# shield_v8.net
KiCad netlist of a schematic drawn in EAGLE
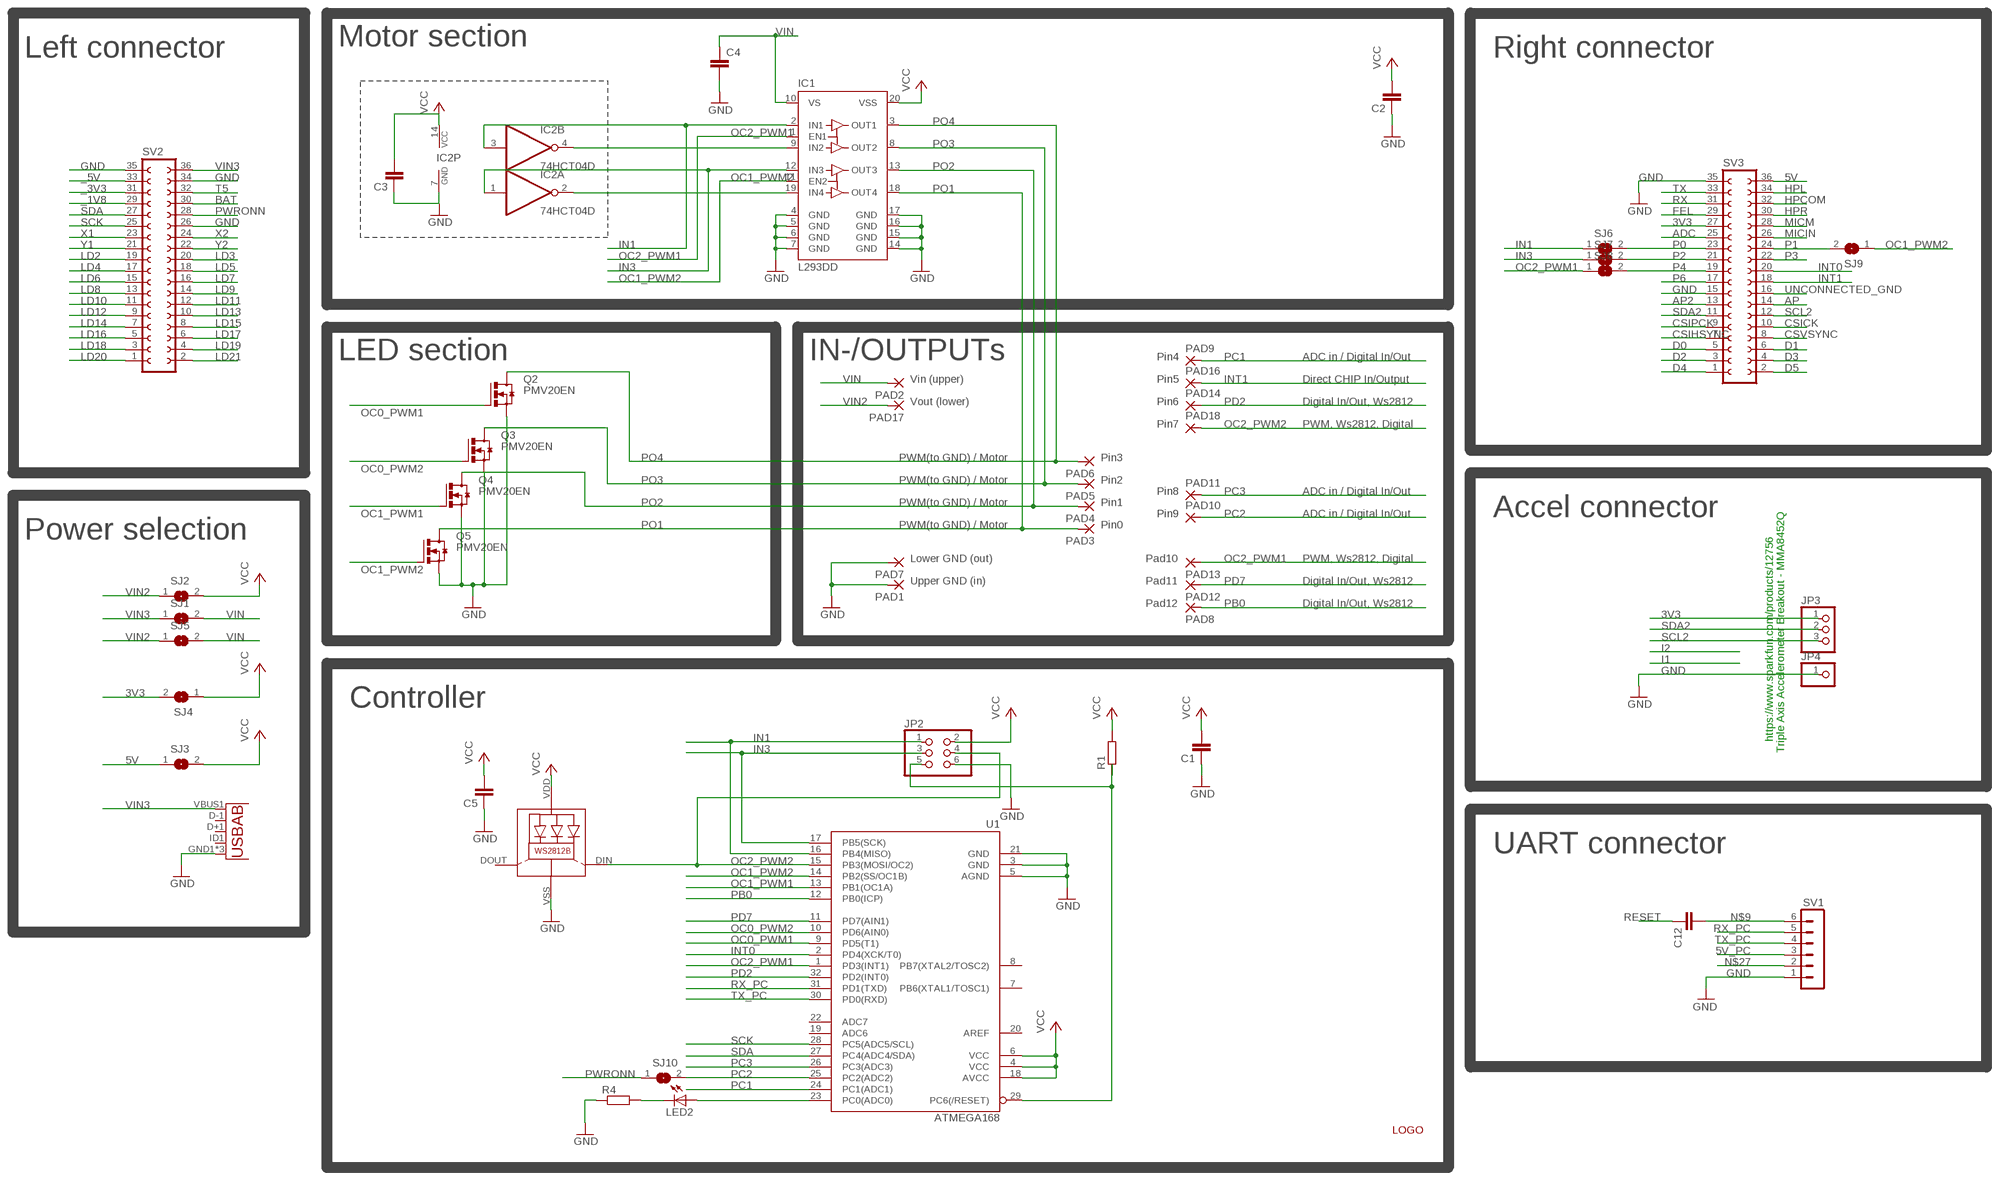
[diagram p0: schematic, sheet 1]

(export (version "E")
  (design (tool "Eeschema 10.0.6"))
  (components
    (comp (ref "C1")
      (value "C-EUC0805")
      (footprint "eagle-import:C0805")
      (libsource (lib "eagle-import") (part "C-EUC0805"))
    )
    (comp (ref "C2")
      (value "C-EUC0805")
      (footprint "eagle-import:C0805")
      (libsource (lib "eagle-import") (part "C-EUC0805"))
    )
    (comp (ref "C3")
      (value "C-EUC0805")
      (footprint "eagle-import:C0805")
      (libsource (lib "eagle-import") (part "C-EUC0805"))
    )
    (comp (ref "C4")
      (value "C-EUC1210")
      (footprint "eagle-import:C1210")
      (libsource (lib "eagle-import") (part "C-EUC1210"))
    )
    (comp (ref "C5")
      (value "C-EUC0805")
      (footprint "eagle-import:C0805")
      (libsource (lib "eagle-import") (part "C-EUC0805"))
    )
    (comp (ref "C12")
      (value "C-EUC1206")
      (footprint "eagle-import:C1206")
      (libsource (lib "eagle-import") (part "C-EUC1206"))
    )
    (comp (ref "IC1")
      (value "L293DD")
      (footprint "eagle-import:SO20")
      (libsource (lib "eagle-import") (part "L293DD"))
    )
    (comp (ref "IC2")
      (value "74HCT04D")
      (footprint "eagle-import:SO14")
      (libsource (lib "eagle-import") (part "7404DHCT"))
    )
    (comp (ref "JP2")
      (value "PINHD-2X3")
      (footprint "eagle-import:2X03")
      (libsource (lib "eagle-import") (part "PINHD-2X3"))
    )
    (comp (ref "JP3")
      (value "PINHD-1X3")
      (footprint "eagle-import:1X03")
      (libsource (lib "eagle-import") (part "PINHD-1X3"))
    )
    (comp (ref "JP4")
      (value "PINHD-1X1")
      (footprint "eagle-import:1X01")
      (libsource (lib "eagle-import") (part "PINHD-1X1"))
    )
    (comp (ref "LED1")
      (value "WS2812B")
      (footprint "eagle-import:WS2812B")
      (libsource (lib "eagle-import") (part "WS2812B"))
    )
    (comp (ref "LED2")
      (value "LEDCHIP-LED0805")
      (footprint "eagle-import:CHIP-LED0805")
      (libsource (lib "eagle-import") (part "LEDCHIP-LED0805"))
    )
    (comp (ref "PAD1")
      (value "3,17/1,3")
      (footprint "eagle-import:3,17_1,3")
      (libsource (lib "eagle-import") (part "3,17/1,3"))
    )
    (comp (ref "PAD2")
      (value "3,17/1,3")
      (footprint "eagle-import:3,17_1,3")
      (libsource (lib "eagle-import") (part "3,17/1,3"))
    )
    (comp (ref "PAD3")
      (value "3,17/1,3")
      (footprint "eagle-import:3,17_1,3")
      (libsource (lib "eagle-import") (part "3,17/1,3"))
    )
    (comp (ref "PAD4")
      (value "3,17/1,3")
      (footprint "eagle-import:3,17_1,3")
      (libsource (lib "eagle-import") (part "3,17/1,3"))
    )
    (comp (ref "PAD5")
      (value "3,17/1,3")
      (footprint "eagle-import:3,17_1,3")
      (libsource (lib "eagle-import") (part "3,17/1,3"))
    )
    (comp (ref "PAD6")
      (value "3,17/1,3")
      (footprint "eagle-import:3,17_1,3")
      (libsource (lib "eagle-import") (part "3,17/1,3"))
    )
    (comp (ref "PAD7")
      (value "3,17/1,3")
      (footprint "eagle-import:3,17_1,3")
      (libsource (lib "eagle-import") (part "3,17/1,3"))
    )
    (comp (ref "PAD8")
      (value "WIREPADSMD1,27-254")
      (footprint "eagle-import:SMD1,27-2,54")
      (libsource (lib "eagle-import") (part "WIREPADSMD1,27-254"))
    )
    (comp (ref "PAD9")
      (value "3,17/1,3")
      (footprint "eagle-import:3,17_1,3")
      (libsource (lib "eagle-import") (part "3,17/1,3"))
    )
    (comp (ref "PAD10")
      (value "3,17/1,3")
      (footprint "eagle-import:3,17_1,3")
      (libsource (lib "eagle-import") (part "3,17/1,3"))
    )
    (comp (ref "PAD11")
      (value "3,17/1,3")
      (footprint "eagle-import:3,17_1,3")
      (libsource (lib "eagle-import") (part "3,17/1,3"))
    )
    (comp (ref "PAD12")
      (value "SMD2")
      (footprint "eagle-import:SMD1,27-2,54")
      (libsource (lib "eagle-import") (part "SMD2"))
    )
    (comp (ref "PAD13")
      (value "SMD2")
      (footprint "eagle-import:SMD1,27-2,54")
      (libsource (lib "eagle-import") (part "SMD2"))
    )
    (comp (ref "PAD14")
      (value "3,17/1,3")
      (footprint "eagle-import:3,17_1,3")
      (libsource (lib "eagle-import") (part "3,17/1,3"))
    )
    (comp (ref "PAD16")
      (value "3,17/1,3")
      (footprint "eagle-import:3,17_1,3")
      (libsource (lib "eagle-import") (part "3,17/1,3"))
    )
    (comp (ref "PAD17")
      (value "3,17/1,3")
      (footprint "eagle-import:3,17_1,3")
      (libsource (lib "eagle-import") (part "3,17/1,3"))
    )
    (comp (ref "PAD18")
      (value "3,17/1,3")
      (footprint "eagle-import:3,17_1,3")
      (libsource (lib "eagle-import") (part "3,17/1,3"))
    )
    (comp (ref "Q2")
      (value "PMV20EN")
      (footprint "eagle-import:SOT223")
      (libsource (lib "eagle-import") (part "NMOSFET_SMD_223"))
    )
    (comp (ref "Q3")
      (value "PMV20EN")
      (footprint "eagle-import:SOT223")
      (libsource (lib "eagle-import") (part "NMOSFET_SMD_223"))
    )
    (comp (ref "Q4")
      (value "PMV20EN")
      (footprint "eagle-import:SOT223")
      (libsource (lib "eagle-import") (part "NMOSFET_SMD_223"))
    )
    (comp (ref "Q5")
      (value "PMV20EN")
      (footprint "eagle-import:SOT223")
      (libsource (lib "eagle-import") (part "NMOSFET_SMD_223"))
    )
    (comp (ref "R1")
      (value "R-EU_M1206")
      (footprint "eagle-import:M1206")
      (libsource (lib "eagle-import") (part "R-EU_M1206"))
    )
    (comp (ref "R4")
      (value "R-EU_M1206")
      (footprint "eagle-import:M1206")
      (libsource (lib "eagle-import") (part "R-EU_M1206"))
    )
    (comp (ref "SJ1") (value "SJ") (footprint "eagle-import:SJ") (libsource (lib "eagle-import") (part "SJ")))
    (comp (ref "SJ2") (value "SJ") (footprint "eagle-import:SJ") (libsource (lib "eagle-import") (part "SJ")))
    (comp (ref "SJ3") (value "SJ") (footprint "eagle-import:SJ") (libsource (lib "eagle-import") (part "SJ")))
    (comp (ref "SJ4") (value "SJ") (footprint "eagle-import:SJ") (libsource (lib "eagle-import") (part "SJ")))
    (comp (ref "SJ5") (value "SJ") (footprint "eagle-import:SJ") (libsource (lib "eagle-import") (part "SJ")))
    (comp (ref "SJ6") (value "SJ") (footprint "eagle-import:SJ") (libsource (lib "eagle-import") (part "SJ")))
    (comp (ref "SJ7") (value "SJ") (footprint "eagle-import:SJ") (libsource (lib "eagle-import") (part "SJ")))
    (comp (ref "SJ8") (value "SJ") (footprint "eagle-import:SJ") (libsource (lib "eagle-import") (part "SJ")))
    (comp (ref "SJ9") (value "SJ") (footprint "eagle-import:SJ") (libsource (lib "eagle-import") (part "SJ")))
    (comp (ref "SJ10")
      (value "SJ")
      (footprint "eagle-import:SJ")
      (libsource (lib "eagle-import") (part "SJ"))
    )
    (comp (ref "SV1")
      (value "MA06-1")
      (footprint "eagle-import:MA06-1")
      (libsource (lib "eagle-import") (part "MA06-1"))
    )
    (comp (ref "SV2")
      (value "FE18-2")
      (footprint "eagle-import:FE18-2")
      (libsource (lib "eagle-import") (part "FE18-2"))
    )
    (comp (ref "SV3")
      (value "FE18-2")
      (footprint "eagle-import:FE18-2")
      (libsource (lib "eagle-import") (part "FE18-2"))
    )
    (comp (ref "U$2")
      (value "LOGO")
      (footprint "eagle-import:LOGO")
      (libsource (lib "eagle-import") (part "LOGO"))
    )
    (comp (ref "U1")
      (value "ATMEGA168")
      (footprint "eagle-import:TQFP32-08")
      (libsource (lib "eagle-import") (part "ATMEGA168"))
    )
    (comp (ref "U2")
      (value "USB\"\"")
      (footprint "eagle-import:USB-MICRO-SMD")
      (libsource (lib "eagle-import") (part "USB{dblquote}{dblquote}"))
    )
  )
  (nets
    (net (code "1") (name "/3V3") (class "Default")
      (node (ref "JP3") (pin "1") (pinfunction "1_1") (pintype "passive"))
      (node (ref "SJ4") (pin "2") (pinfunction "2_2") (pintype "passive"))
      (node (ref "SV3") (pin "27") (pinfunction "27_27") (pintype "passive"))
    )
    (net (code "2") (name "/5V") (class "Default")
      (node (ref "SJ3") (pin "1") (pinfunction "1_1") (pintype "passive"))
      (node (ref "SV3") (pin "36") (pinfunction "36_36") (pintype "passive"))
    )
    (net (code "3") (name "/5V_PC") (class "Default")
      (node (ref "SV1") (pin "3") (pinfunction "3_3") (pintype "passive"))
    )
    (net (code "4") (name "/ADC") (class "Default")
      (node (ref "SV3") (pin "25") (pinfunction "25_25") (pintype "passive"))
    )
    (net (code "5") (name "/AP") (class "Default")
      (node (ref "SV3") (pin "14") (pinfunction "14_14") (pintype "passive"))
    )
    (net (code "6") (name "/AP2") (class "Default")
      (node (ref "SV3") (pin "13") (pinfunction "13_13") (pintype "passive"))
    )
    (net (code "7") (name "/BAT") (class "Default")
      (node (ref "SV2") (pin "30") (pinfunction "30_30") (pintype "passive"))
    )
    (net (code "8") (name "/CSICK") (class "Default")
      (node (ref "SV3") (pin "10") (pinfunction "10_10") (pintype "passive"))
    )
    (net (code "9") (name "/CSIHSYNC") (class "Default")
      (node (ref "SV3") (pin "7") (pinfunction "7_7") (pintype "passive"))
    )
    (net (code "10") (name "/CSIPCK") (class "Default")
      (node (ref "SV3") (pin "9") (pinfunction "9_9") (pintype "passive"))
    )
    (net (code "11") (name "/CSVSYNC") (class "Default")
      (node (ref "SV3") (pin "8") (pinfunction "8_8") (pintype "passive"))
    )
    (net (code "12") (name "/D0") (class "Default")
      (node (ref "SV3") (pin "5") (pinfunction "5_5") (pintype "passive"))
    )
    (net (code "13") (name "/D1") (class "Default")
      (node (ref "SV3") (pin "6") (pinfunction "6_6") (pintype "passive"))
    )
    (net (code "14") (name "/D2") (class "Default")
      (node (ref "SV3") (pin "3") (pinfunction "3_3") (pintype "passive"))
    )
    (net (code "15") (name "/D3") (class "Default")
      (node (ref "SV3") (pin "4") (pinfunction "4_4") (pintype "passive"))
    )
    (net (code "16") (name "/D4") (class "Default")
      (node (ref "SV3") (pin "1") (pinfunction "1_1") (pintype "passive"))
    )
    (net (code "17") (name "/D5") (class "Default")
      (node (ref "SV3") (pin "2") (pinfunction "2_2") (pintype "passive"))
    )
    (net (code "18") (name "/FEL") (class "Default")
      (node (ref "SV3") (pin "29") (pinfunction "29_29") (pintype "passive"))
    )
    (net (code "19") (name "/HPCOM") (class "Default")
      (node (ref "SV3") (pin "32") (pinfunction "32_32") (pintype "passive"))
    )
    (net (code "20") (name "/HPL") (class "Default")
      (node (ref "SV3") (pin "34") (pinfunction "34_34") (pintype "passive"))
    )
    (net (code "21") (name "/HPR") (class "Default")
      (node (ref "SV3") (pin "30") (pinfunction "30_30") (pintype "passive"))
    )
    (net (code "24") (name "/IN1") (class "Default")
      (node (ref "IC1") (pin "2") (pinfunction "IN1_2") (pintype "input"))
      (node (ref "IC2") (pin "3") (pinfunction "I_3") (pintype "input"))
      (node (ref "JP2") (pin "1") (pinfunction "1_1") (pintype "passive"))
      (node (ref "SJ6") (pin "1") (pinfunction "1_1") (pintype "passive"))
      (node (ref "U1") (pin "16") (pinfunction "PB4(MISO)_16") (pintype "bidirectional"))
    )
    (net (code "25") (name "/IN3") (class "Default")
      (node (ref "IC1") (pin "12") (pinfunction "IN3_12") (pintype "input"))
      (node (ref "IC2") (pin "1") (pinfunction "I_1") (pintype "input"))
      (node (ref "JP2") (pin "3") (pinfunction "3_3") (pintype "passive"))
      (node (ref "SJ7") (pin "1") (pinfunction "1_1") (pintype "passive"))
      (node (ref "U1") (pin "17") (pinfunction "PB5(SCK)_17") (pintype "bidirectional"))
    )
    (net (code "26") (name "/INT0") (class "Default")
      (node (ref "SV3") (pin "20") (pinfunction "20_20") (pintype "passive"))
      (node (ref "U1") (pin "2") (pinfunction "PD4(XCK/T0)_2") (pintype "bidirectional"))
    )
    (net (code "27") (name "/INT1") (class "Default")
      (node (ref "PAD16") (pin "1") (pinfunction "P_1") (pintype "passive"))
      (node (ref "SV3") (pin "18") (pinfunction "18_18") (pintype "passive"))
    )
    (net (code "28") (name "/LD2") (class "Default")
      (node (ref "SV2") (pin "19") (pinfunction "19_19") (pintype "passive"))
    )
    (net (code "29") (name "/LD3") (class "Default")
      (node (ref "SV2") (pin "20") (pinfunction "20_20") (pintype "passive"))
    )
    (net (code "30") (name "/LD4") (class "Default")
      (node (ref "SV2") (pin "17") (pinfunction "17_17") (pintype "passive"))
    )
    (net (code "31") (name "/LD5") (class "Default")
      (node (ref "SV2") (pin "18") (pinfunction "18_18") (pintype "passive"))
    )
    (net (code "32") (name "/LD6") (class "Default")
      (node (ref "SV2") (pin "15") (pinfunction "15_15") (pintype "passive"))
    )
    (net (code "33") (name "/LD7") (class "Default")
      (node (ref "SV2") (pin "16") (pinfunction "16_16") (pintype "passive"))
    )
    (net (code "34") (name "/LD8") (class "Default")
      (node (ref "SV2") (pin "13") (pinfunction "13_13") (pintype "passive"))
    )
    (net (code "35") (name "/LD9") (class "Default")
      (node (ref "SV2") (pin "14") (pinfunction "14_14") (pintype "passive"))
    )
    (net (code "36") (name "/LD10") (class "Default")
      (node (ref "SV2") (pin "11") (pinfunction "11_11") (pintype "passive"))
    )
    (net (code "37") (name "/LD11") (class "Default")
      (node (ref "SV2") (pin "12") (pinfunction "12_12") (pintype "passive"))
    )
    (net (code "38") (name "/LD12") (class "Default")
      (node (ref "SV2") (pin "9") (pinfunction "9_9") (pintype "passive"))
    )
    (net (code "39") (name "/LD13") (class "Default")
      (node (ref "SV2") (pin "10") (pinfunction "10_10") (pintype "passive"))
    )
    (net (code "40") (name "/LD14") (class "Default")
      (node (ref "SV2") (pin "7") (pinfunction "7_7") (pintype "passive"))
    )
    (net (code "41") (name "/LD15") (class "Default")
      (node (ref "SV2") (pin "8") (pinfunction "8_8") (pintype "passive"))
    )
    (net (code "42") (name "/LD16") (class "Default")
      (node (ref "SV2") (pin "5") (pinfunction "5_5") (pintype "passive"))
    )
    (net (code "43") (name "/LD17") (class "Default")
      (node (ref "SV2") (pin "6") (pinfunction "6_6") (pintype "passive"))
    )
    (net (code "44") (name "/LD18") (class "Default")
      (node (ref "SV2") (pin "3") (pinfunction "3_3") (pintype "passive"))
    )
    (net (code "45") (name "/LD19") (class "Default")
      (node (ref "SV2") (pin "4") (pinfunction "4_4") (pintype "passive"))
    )
    (net (code "46") (name "/LD20") (class "Default")
      (node (ref "SV2") (pin "1") (pinfunction "1_1") (pintype "passive"))
    )
    (net (code "47") (name "/LD21") (class "Default")
      (node (ref "SV2") (pin "2") (pinfunction "2_2") (pintype "passive"))
    )
    (net (code "48") (name "/MICIN") (class "Default")
      (node (ref "SV3") (pin "26") (pinfunction "26_26") (pintype "passive"))
    )
    (net (code "49") (name "/MICM") (class "Default")
      (node (ref "SV3") (pin "28") (pinfunction "28_28") (pintype "passive"))
    )
    (net (code "50") (name "/N$9") (class "Default")
      (node (ref "C12") (pin "2") (pinfunction "2_2") (pintype "passive"))
      (node (ref "SV1") (pin "6") (pinfunction "6_6") (pintype "passive"))
    )
    (net (code "51") (name "/N$27") (class "Default")
      (node (ref "SV1") (pin "2") (pinfunction "2_2") (pintype "passive"))
    )
    (net (code "52") (name "/OC0_PWM1") (class "Default")
      (node (ref "Q2") (pin "1") (pinfunction "G_1") (pintype "passive"))
      (node (ref "U1") (pin "9") (pinfunction "PD5(T1)_9") (pintype "bidirectional"))
    )
    (net (code "53") (name "/OC0_PWM2") (class "Default")
      (node (ref "Q3") (pin "1") (pinfunction "G_1") (pintype "passive"))
      (node (ref "U1") (pin "10") (pinfunction "PD6(AIN0)_10") (pintype "bidirectional"))
    )
    (net (code "54") (name "/OC1_PWM1") (class "Default")
      (node (ref "Q4") (pin "1") (pinfunction "G_1") (pintype "passive"))
      (node (ref "U1") (pin "13") (pinfunction "PB1(OC1A)_13") (pintype "bidirectional"))
    )
    (net (code "55") (name "/OC1_PWM2") (class "Default")
      (node (ref "IC1") (pin "11") (pinfunction "EN2_11") (pintype "input"))
      (node (ref "Q5") (pin "1") (pinfunction "G_1") (pintype "passive"))
      (node (ref "SJ9") (pin "1") (pinfunction "1_1") (pintype "passive"))
      (node (ref "U1") (pin "14") (pinfunction "PB2(SS/OC1B)_14") (pintype "bidirectional"))
    )
    (net (code "56") (name "/OC2_PWM1") (class "Default")
      (node (ref "IC1") (pin "1") (pinfunction "EN1_1") (pintype "input"))
      (node (ref "PAD13") (pin "1") (pinfunction "P_1") (pintype "passive"))
      (node (ref "SJ8") (pin "1") (pinfunction "1_1") (pintype "passive"))
      (node (ref "U1") (pin "1") (pinfunction "PD3(INT1)_1") (pintype "bidirectional"))
    )
    (net (code "57") (name "/OC2_PWM2") (class "Default")
      (node (ref "JP2") (pin "4") (pinfunction "4_4") (pintype "passive"))
      (node (ref "LED1") (pin "DIN") (pinfunction "DI_DIN") (pintype "input"))
      (node (ref "PAD18") (pin "1") (pinfunction "P_1") (pintype "passive"))
      (node (ref "U1") (pin "15") (pinfunction "PB3(MOSI/OC2)_15") (pintype "bidirectional"))
    )
    (net (code "58") (name "/P0") (class "Default")
      (node (ref "SJ6") (pin "2") (pinfunction "2_2") (pintype "passive"))
      (node (ref "SV3") (pin "23") (pinfunction "23_23") (pintype "passive"))
    )
    (net (code "59") (name "/P1") (class "Default")
      (node (ref "SJ9") (pin "2") (pinfunction "2_2") (pintype "passive"))
      (node (ref "SV3") (pin "24") (pinfunction "24_24") (pintype "passive"))
    )
    (net (code "60") (name "/P2") (class "Default")
      (node (ref "SJ7") (pin "2") (pinfunction "2_2") (pintype "passive"))
      (node (ref "SV3") (pin "21") (pinfunction "21_21") (pintype "passive"))
    )
    (net (code "61") (name "/P3") (class "Default")
      (node (ref "SV3") (pin "22") (pinfunction "22_22") (pintype "passive"))
    )
    (net (code "62") (name "/P4") (class "Default")
      (node (ref "SJ8") (pin "2") (pinfunction "2_2") (pintype "passive"))
      (node (ref "SV3") (pin "19") (pinfunction "19_19") (pintype "passive"))
    )
    (net (code "63") (name "/P6") (class "Default")
      (node (ref "SV3") (pin "17") (pinfunction "17_17") (pintype "passive"))
    )
    (net (code "64") (name "/PB0") (class "Default")
      (node (ref "PAD8") (pin "1") (pinfunction "P_1") (pintype "passive"))
      (node (ref "U1") (pin "12") (pinfunction "PB0(ICP)_12") (pintype "bidirectional"))
    )
    (net (code "65") (name "/PC1") (class "Default")
      (node (ref "PAD9") (pin "1") (pinfunction "P_1") (pintype "passive"))
      (node (ref "U1") (pin "24") (pinfunction "PC1(ADC1)_24") (pintype "bidirectional"))
    )
    (net (code "66") (name "/PC2") (class "Default")
      (node (ref "PAD10") (pin "1") (pinfunction "P_1") (pintype "passive"))
      (node (ref "SJ10") (pin "2") (pinfunction "2_2") (pintype "passive"))
      (node (ref "U1") (pin "25") (pinfunction "PC2(ADC2)_25") (pintype "bidirectional"))
    )
    (net (code "67") (name "/PC3") (class "Default")
      (node (ref "PAD11") (pin "1") (pinfunction "P_1") (pintype "passive"))
      (node (ref "U1") (pin "26") (pinfunction "PC3(ADC3)_26") (pintype "bidirectional"))
    )
    (net (code "68") (name "/PD2") (class "Default")
      (node (ref "PAD14") (pin "1") (pinfunction "P_1") (pintype "passive"))
      (node (ref "U1") (pin "32") (pinfunction "PD2(INT0)_32") (pintype "bidirectional"))
    )
    (net (code "69") (name "/PD7") (class "Default")
      (node (ref "PAD12") (pin "1") (pinfunction "P_1") (pintype "passive"))
      (node (ref "U1") (pin "11") (pinfunction "PD7(AIN1)_11") (pintype "bidirectional"))
    )
    (net (code "70") (name "/PO1") (class "Default")
      (node (ref "IC1") (pin "18") (pinfunction "OUT4_18") (pintype "output"))
      (node (ref "PAD3") (pin "1") (pinfunction "P_1") (pintype "passive"))
      (node (ref "Q5") (pin "2") (pinfunction "D_2") (pintype "passive"))
      (node (ref "Q5") (pin "4") (pinfunction "D_4") (pintype "passive"))
    )
    (net (code "71") (name "/PO2") (class "Default")
      (node (ref "IC1") (pin "13") (pinfunction "OUT3_13") (pintype "output"))
      (node (ref "PAD4") (pin "1") (pinfunction "P_1") (pintype "passive"))
      (node (ref "Q4") (pin "2") (pinfunction "D_2") (pintype "passive"))
      (node (ref "Q4") (pin "4") (pinfunction "D_4") (pintype "passive"))
    )
    (net (code "72") (name "/PO3") (class "Default")
      (node (ref "IC1") (pin "8") (pinfunction "OUT2_8") (pintype "output"))
      (node (ref "PAD5") (pin "1") (pinfunction "P_1") (pintype "passive"))
      (node (ref "Q3") (pin "2") (pinfunction "D_2") (pintype "passive"))
      (node (ref "Q3") (pin "4") (pinfunction "D_4") (pintype "passive"))
    )
    (net (code "73") (name "/PO4") (class "Default")
      (node (ref "IC1") (pin "3") (pinfunction "OUT1_3") (pintype "output"))
      (node (ref "PAD6") (pin "1") (pinfunction "P_1") (pintype "passive"))
      (node (ref "Q2") (pin "2") (pinfunction "D_2") (pintype "passive"))
      (node (ref "Q2") (pin "4") (pinfunction "D_4") (pintype "passive"))
    )
    (net (code "74") (name "/PWRONN") (class "Default")
      (node (ref "SJ10") (pin "1") (pinfunction "1_1") (pintype "passive"))
      (node (ref "SV2") (pin "28") (pinfunction "28_28") (pintype "passive"))
    )
    (net (code "75") (name "/RESET") (class "Default")
      (node (ref "C12") (pin "1") (pinfunction "1_1") (pintype "passive"))
      (node (ref "JP2") (pin "5") (pinfunction "5_5") (pintype "passive"))
      (node (ref "R1") (pin "1") (pinfunction "1_1") (pintype "passive"))
      (node (ref "U1") (pin "29") (pinfunction "PC6(/RESET)_29") (pintype "bidirectional"))
    )
    (net (code "76") (name "/RX") (class "Default")
      (node (ref "SV3") (pin "31") (pinfunction "31_31") (pintype "passive"))
    )
    (net (code "77") (name "/RX_PC") (class "Default")
      (node (ref "SV1") (pin "5") (pinfunction "5_5") (pintype "passive"))
      (node (ref "U1") (pin "31") (pinfunction "PD1(TXD)_31") (pintype "bidirectional"))
    )
    (net (code "78") (name "/SCK") (class "Default")
      (node (ref "SV2") (pin "25") (pinfunction "25_25") (pintype "passive"))
      (node (ref "U1") (pin "28") (pinfunction "PC5(ADC5/SCL)_28") (pintype "bidirectional"))
    )
    (net (code "79") (name "/SCL2") (class "Default")
      (node (ref "JP3") (pin "3") (pinfunction "3_3") (pintype "passive"))
      (node (ref "SV3") (pin "12") (pinfunction "12_12") (pintype "passive"))
    )
    (net (code "80") (name "/SDA") (class "Default")
      (node (ref "SV2") (pin "27") (pinfunction "27_27") (pintype "passive"))
      (node (ref "U1") (pin "27") (pinfunction "PC4(ADC4/SDA)_27") (pintype "bidirectional"))
    )
    (net (code "81") (name "/SDA2") (class "Default")
      (node (ref "JP3") (pin "2") (pinfunction "2_2") (pintype "passive"))
      (node (ref "SV3") (pin "11") (pinfunction "11_11") (pintype "passive"))
    )
    (net (code "82") (name "/T5") (class "Default")
      (node (ref "SV2") (pin "32") (pinfunction "32_32") (pintype "passive"))
    )
    (net (code "83") (name "/TX") (class "Default")
      (node (ref "SV3") (pin "33") (pinfunction "33_33") (pintype "passive"))
    )
    (net (code "84") (name "/TX_PC") (class "Default")
      (node (ref "SV1") (pin "4") (pinfunction "4_4") (pintype "passive"))
      (node (ref "U1") (pin "30") (pinfunction "PD0(RXD)_30") (pintype "bidirectional"))
    )
    (net (code "85") (name "/UNCONNECTED_GND") (class "Default")
      (node (ref "SV3") (pin "16") (pinfunction "16_16") (pintype "passive"))
    )
    (net (code "86") (name "/VIN") (class "Default")
      (node (ref "C4") (pin "1") (pinfunction "1_1") (pintype "passive"))
      (node (ref "IC1") (pin "10") (pinfunction "VS_10") (pintype "power_in"))
      (node (ref "PAD2") (pin "1") (pinfunction "P_1") (pintype "passive"))
      (node (ref "SJ1") (pin "2") (pinfunction "2_2") (pintype "passive"))
      (node (ref "SJ5") (pin "2") (pinfunction "2_2") (pintype "passive"))
    )
    (net (code "87") (name "/VIN2") (class "Default")
      (node (ref "PAD17") (pin "1") (pinfunction "P_1") (pintype "passive"))
      (node (ref "SJ2") (pin "1") (pinfunction "1_1") (pintype "passive"))
      (node (ref "SJ5") (pin "1") (pinfunction "1_1") (pintype "passive"))
    )
    (net (code "88") (name "/VIN3") (class "Default")
      (node (ref "SJ1") (pin "1") (pinfunction "1_1") (pintype "passive"))
      (node (ref "SV2") (pin "36") (pinfunction "36_36") (pintype "passive"))
      (node (ref "U2") (pin "VBUS1") (pinfunction "VBUS_VBUS1") (pintype "bidirectional"))
    )
    (net (code "89") (name "/X1") (class "Default")
      (node (ref "SV2") (pin "23") (pinfunction "23_23") (pintype "passive"))
    )
    (net (code "90") (name "/X2") (class "Default")
      (node (ref "SV2") (pin "24") (pinfunction "24_24") (pintype "passive"))
    )
    (net (code "91") (name "/Y1") (class "Default")
      (node (ref "SV2") (pin "21") (pinfunction "21_21") (pintype "passive"))
    )
    (net (code "92") (name "/Y2") (class "Default")
      (node (ref "SV2") (pin "22") (pinfunction "22_22") (pintype "passive"))
    )
    (net (code "93") (name "/_1V8") (class "Default")
      (node (ref "SV2") (pin "29") (pinfunction "29_29") (pintype "passive"))
    )
    (net (code "94") (name "/_3V3") (class "Default")
      (node (ref "SV2") (pin "31") (pinfunction "31_31") (pintype "passive"))
    )
    (net (code "95") (name "/_5V") (class "Default")
      (node (ref "SV2") (pin "33") (pinfunction "33_33") (pintype "passive"))
    )
    (net (code "96") (name "GND") (class "Default")
      (node (ref "C1") (pin "1") (pinfunction "1_1") (pintype "passive"))
      (node (ref "C2") (pin "1") (pinfunction "1_1") (pintype "passive"))
      (node (ref "C3") (pin "1") (pinfunction "1_1") (pintype "passive"))
      (node (ref "C4") (pin "2") (pinfunction "2_2") (pintype "passive"))
      (node (ref "C5") (pin "1") (pinfunction "1_1") (pintype "passive"))
      (node (ref "IC1") (pin "14") (pinfunction "GND_14") (pintype "power_in"))
      (node (ref "IC1") (pin "15") (pinfunction "GND_15") (pintype "power_in"))
      (node (ref "IC1") (pin "16") (pinfunction "GND_16") (pintype "power_in"))
      (node (ref "IC1") (pin "17") (pinfunction "GND_17") (pintype "power_in"))
      (node (ref "IC1") (pin "4") (pinfunction "GND_4") (pintype "power_in"))
      (node (ref "IC1") (pin "5") (pinfunction "GND_5") (pintype "power_in"))
      (node (ref "IC1") (pin "6") (pinfunction "GND_6") (pintype "power_in"))
      (node (ref "IC1") (pin "7") (pinfunction "GND_7") (pintype "power_in"))
      (node (ref "IC2") (pin "7") (pinfunction "GND_7") (pintype "power_in"))
      (node (ref "JP2") (pin "6") (pinfunction "6_6") (pintype "passive"))
      (node (ref "JP4") (pin "1") (pinfunction "1_1") (pintype "passive"))
      (node (ref "LED1") (pin "VSS") (pinfunction "GND_VSS") (pintype "power_in"))
      (node (ref "PAD1") (pin "1") (pinfunction "P_1") (pintype "passive"))
      (node (ref "PAD7") (pin "1") (pinfunction "P_1") (pintype "passive"))
      (node (ref "Q2") (pin "3") (pinfunction "S_3") (pintype "passive"))
      (node (ref "Q3") (pin "3") (pinfunction "S_3") (pintype "passive"))
      (node (ref "Q4") (pin "3") (pinfunction "S_3") (pintype "passive"))
      (node (ref "Q5") (pin "3") (pinfunction "S_3") (pintype "passive"))
      (node (ref "R4") (pin "1") (pinfunction "1_1") (pintype "passive"))
      (node (ref "SV1") (pin "1") (pinfunction "1_1") (pintype "passive"))
      (node (ref "SV2") (pin "26") (pinfunction "26_26") (pintype "passive"))
      (node (ref "SV2") (pin "34") (pinfunction "34_34") (pintype "passive"))
      (node (ref "SV2") (pin "35") (pinfunction "35_35") (pintype "passive"))
      (node (ref "SV3") (pin "15") (pinfunction "15_15") (pintype "passive"))
      (node (ref "SV3") (pin "35") (pinfunction "35_35") (pintype "passive"))
      (node (ref "U1") (pin "21") (pinfunction "GND_21") (pintype "bidirectional"))
      (node (ref "U1") (pin "3") (pinfunction "GND_3") (pintype "bidirectional"))
      (node (ref "U1") (pin "5") (pinfunction "AGND_5") (pintype "bidirectional"))
      (node (ref "U2") (pin "GND1") (pinfunction "GND_GND1") (pintype "bidirectional"))
      (node (ref "U2") (pin "GND2") (pinfunction "GND_GND2") (pintype "bidirectional"))
      (node (ref "U2") (pin "GND3") (pinfunction "GND_GND3") (pintype "bidirectional"))
    )
    (net (code "97") (name "Net-(IC1-IN2)") (class "Default")
      (node (ref "IC1") (pin "9") (pinfunction "IN2_9") (pintype "input"))
      (node (ref "IC2") (pin "4") (pinfunction "O_4") (pintype "output"))
    )
    (net (code "98") (name "Net-(IC1-IN4)") (class "Default")
      (node (ref "IC1") (pin "19") (pinfunction "IN4_19") (pintype "input"))
      (node (ref "IC2") (pin "2") (pinfunction "O_2") (pintype "output"))
    )
    (net (code "99") (name "Net-(LED2-PadC)") (class "Default")
      (node (ref "LED2") (pin "C") (pinfunction "C_C") (pintype "passive"))
      (node (ref "R4") (pin "2") (pinfunction "2_2") (pintype "passive"))
    )
    (net (code "100") (name "Net-(U1-PC0(ADC0))") (class "Default")
      (node (ref "LED2") (pin "A") (pinfunction "A_A") (pintype "passive"))
      (node (ref "U1") (pin "23") (pinfunction "PC0(ADC0)_23") (pintype "bidirectional"))
    )
    (net (code "101") (name "VCC") (class "Default")
      (node (ref "C1") (pin "2") (pinfunction "2_2") (pintype "passive"))
      (node (ref "C2") (pin "2") (pinfunction "2_2") (pintype "passive"))
      (node (ref "C3") (pin "2") (pinfunction "2_2") (pintype "passive"))
      (node (ref "C5") (pin "2") (pinfunction "2_2") (pintype "passive"))
      (node (ref "IC1") (pin "20") (pinfunction "VSS_20") (pintype "power_in"))
      (node (ref "IC2") (pin "14") (pinfunction "VCC_14") (pintype "power_in"))
      (node (ref "JP2") (pin "2") (pinfunction "2_2") (pintype "passive"))
      (node (ref "LED1") (pin "VDD") (pinfunction "VDD_VDD") (pintype "power_in"))
      (node (ref "R1") (pin "2") (pinfunction "2_2") (pintype "passive"))
      (node (ref "SJ2") (pin "2") (pinfunction "2_2") (pintype "passive"))
      (node (ref "SJ3") (pin "2") (pinfunction "2_2") (pintype "passive"))
      (node (ref "SJ4") (pin "1") (pinfunction "1_1") (pintype "passive"))
      (node (ref "U1") (pin "18") (pinfunction "AVCC_18") (pintype "bidirectional"))
      (node (ref "U1") (pin "4") (pinfunction "VCC_4") (pintype "bidirectional"))
      (node (ref "U1") (pin "6") (pinfunction "VCC_6") (pintype "bidirectional"))
    )
    (net (code "102") (name "unconnected-(LED1-DO-PadDOUT)") (class "Default")
      (node (ref "LED1") (pin "DOUT") (pinfunction "DO_DOUT") (pintype "output"))
    )
    (net (code "103") (name "unconnected-(U1-ADC6-Pad19)") (class "Default")
      (node (ref "U1") (pin "19") (pinfunction "ADC6_19") (pintype "bidirectional"))
    )
    (net (code "104") (name "unconnected-(U1-ADC7-Pad22)") (class "Default")
      (node (ref "U1") (pin "22") (pinfunction "ADC7_22") (pintype "bidirectional"))
    )
    (net (code "105") (name "unconnected-(U1-AREF-Pad20)") (class "Default")
      (node (ref "U1") (pin "20") (pinfunction "AREF_20") (pintype "bidirectional"))
    )
    (net (code "106") (name "unconnected-(U1-PB6(XTAL1{slash}TOSC1)-Pad7)") (class "Default")
      (node (ref "U1") (pin "7") (pinfunction "PB6(XTAL1/TOSC1)_7") (pintype "bidirectional"))
    )
    (net (code "107") (name "unconnected-(U1-PB7(XTAL2{slash}TOSC2)-Pad8)") (class "Default")
      (node (ref "U1") (pin "8") (pinfunction "PB7(XTAL2/TOSC2)_8") (pintype "bidirectional"))
    )
    (net (code "108") (name "unconnected-(U2-D+-PadD+1)") (class "Default")
      (node (ref "U2") (pin "D+1") (pinfunction "D+_D+1") (pintype "bidirectional"))
    )
    (net (code "109") (name "unconnected-(U2-D--PadD-1)") (class "Default")
      (node (ref "U2") (pin "D-1") (pinfunction "D-_D-1") (pintype "bidirectional"))
    )
    (net (code "110") (name "unconnected-(U2-USBID-PadID1)") (class "Default")
      (node (ref "U2") (pin "ID1") (pinfunction "USBID_ID1") (pintype "bidirectional"))
    )
  )
)
